# wolf_rev_c.net
KiCad netlist of a schematic drawn in EAGLE
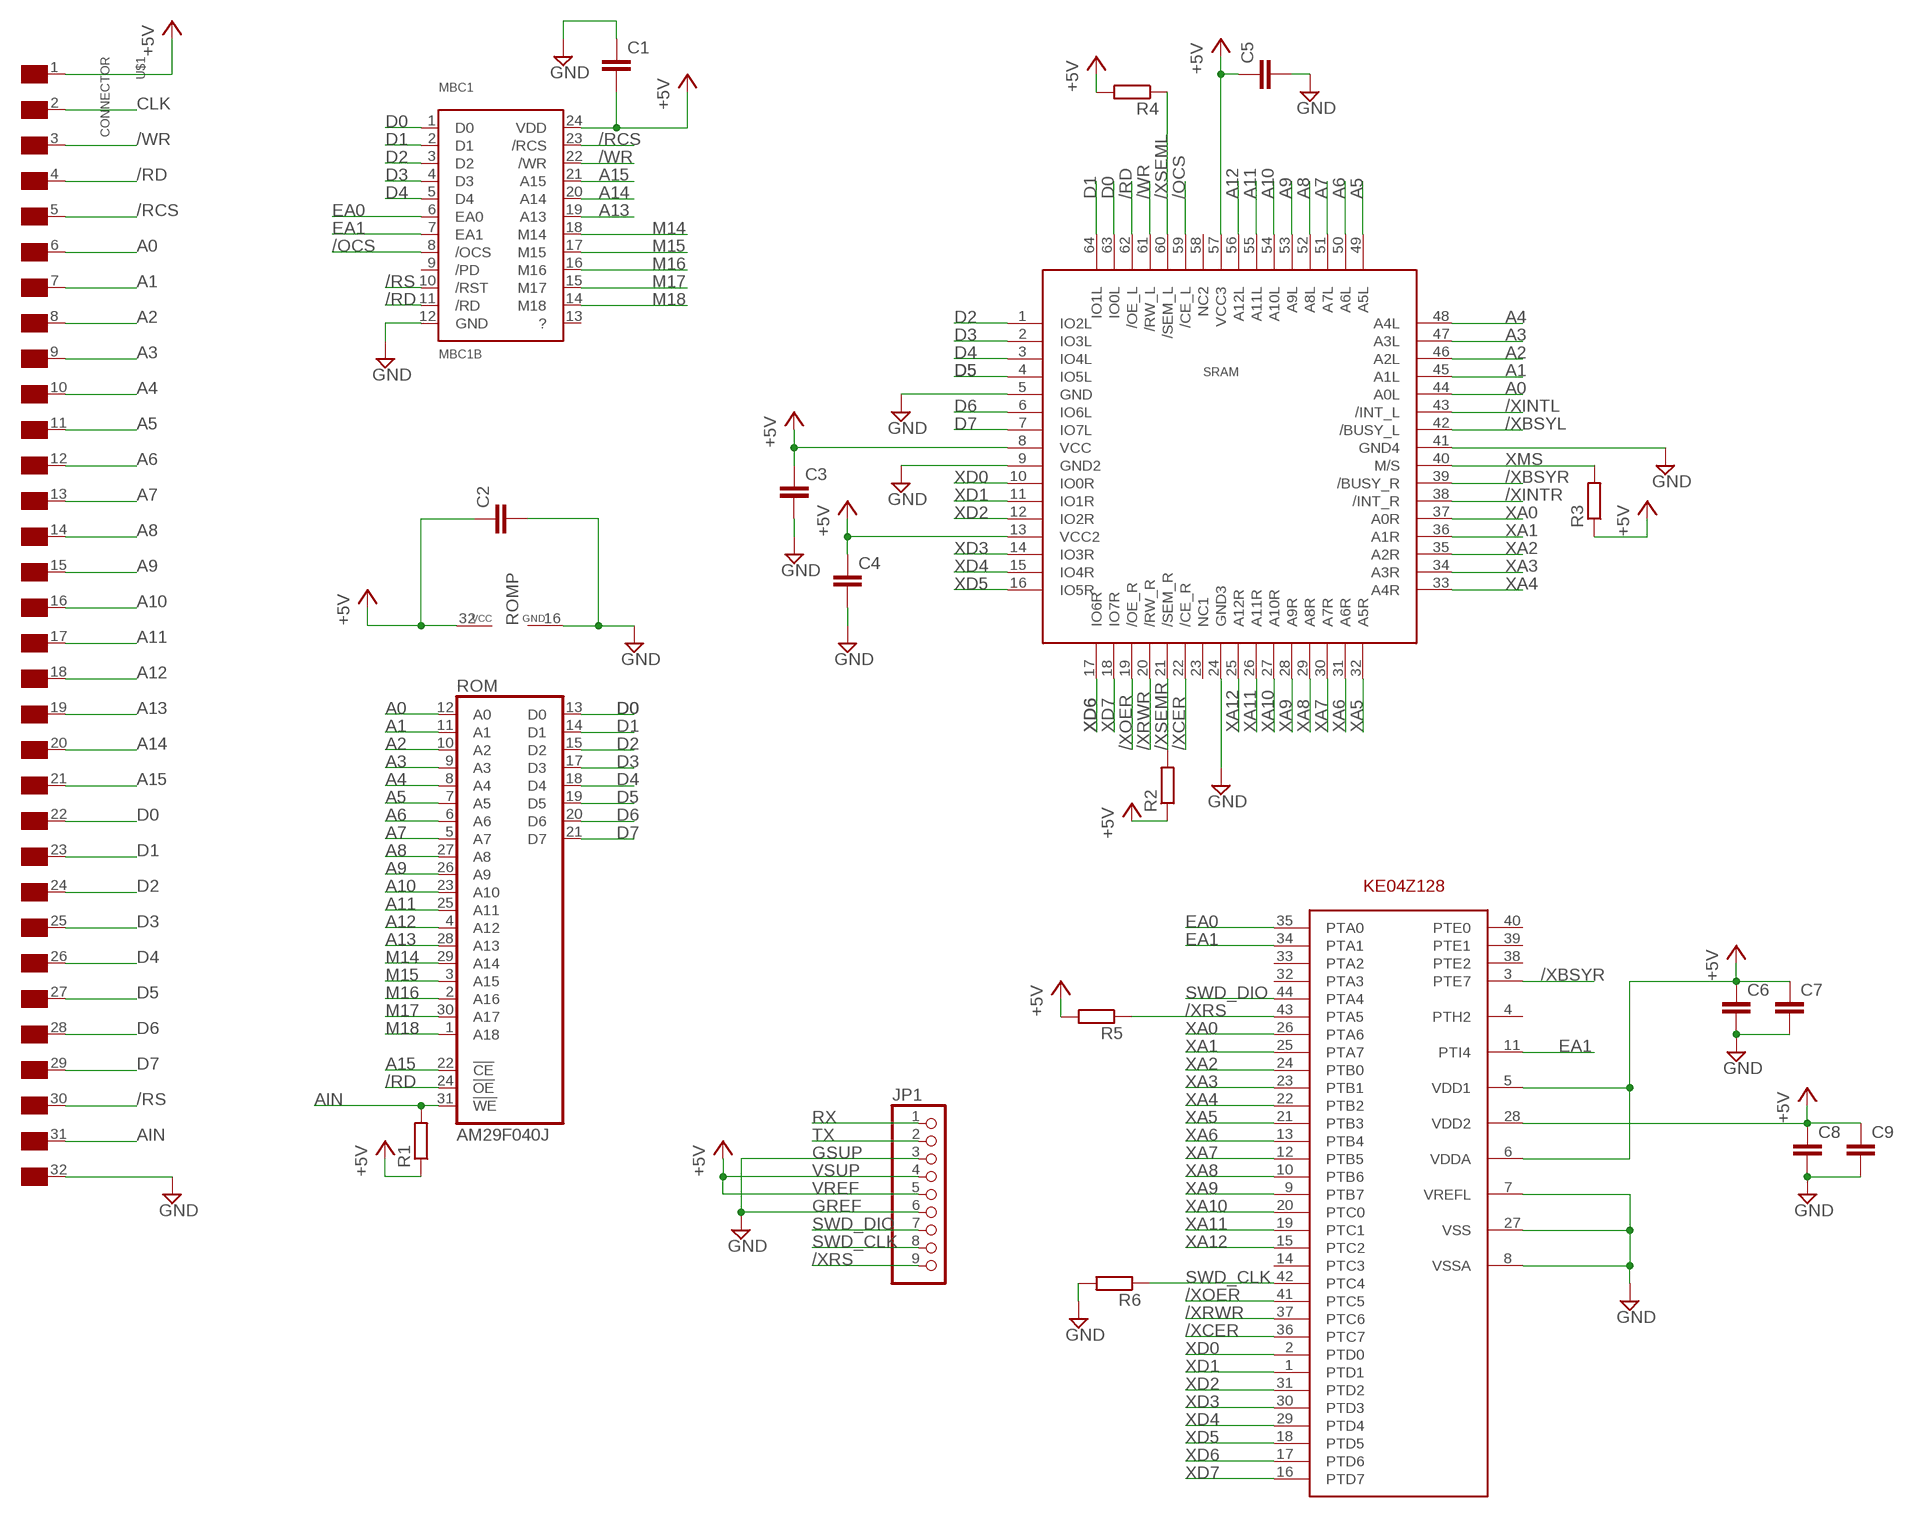
[diagram p0: schematic, sheet 1]

(export (version "E")
  (design (tool "Eeschema 10.0.6"))
  (components
    (comp (ref "C1")
      (value "C-EUC0805")
      (footprint "eagle-import:C0805")
      (libsource (lib "eagle-import") (part "C-EUC0805"))
    )
    (comp (ref "C2")
      (value "C-EUC0805")
      (footprint "eagle-import:C0805")
      (libsource (lib "eagle-import") (part "C-EUC0805"))
    )
    (comp (ref "C3")
      (value "C-EUC0805")
      (footprint "eagle-import:C0805")
      (libsource (lib "eagle-import") (part "C-EUC0805"))
    )
    (comp (ref "C4")
      (value "C-EUC0805")
      (footprint "eagle-import:C0805")
      (libsource (lib "eagle-import") (part "C-EUC0805"))
    )
    (comp (ref "C5")
      (value "C-EUC0805")
      (footprint "eagle-import:C0805")
      (libsource (lib "eagle-import") (part "C-EUC0805"))
    )
    (comp (ref "C6")
      (value "C-EUC0805")
      (footprint "eagle-import:C0805")
      (libsource (lib "eagle-import") (part "C-EUC0805"))
    )
    (comp (ref "C7")
      (value "C-EUC0805")
      (footprint "eagle-import:C0805")
      (libsource (lib "eagle-import") (part "C-EUC0805"))
    )
    (comp (ref "C8")
      (value "C-EUC0805")
      (footprint "eagle-import:C0805")
      (libsource (lib "eagle-import") (part "C-EUC0805"))
    )
    (comp (ref "C9")
      (value "C-EUC0805")
      (footprint "eagle-import:C0805")
      (libsource (lib "eagle-import") (part "C-EUC0805"))
    )
    (comp (ref "JP1")
      (value "PINHD-1X9")
      (footprint "eagle-import:1X09")
      (libsource (lib "eagle-import") (part "PINHD-1X9"))
    )
    (comp (ref "KE04Z128")
      (value "KE04Z128")
      (footprint "eagle-import:TQFP44")
      (libsource (lib "eagle-import") (part "KE04Z128VLD4"))
    )
    (comp (ref "MBC1")
      (value "MBC1B")
      (footprint "eagle-import:MBC1B")
      (libsource (lib "eagle-import") (part "MBC1B"))
    )
    (comp (ref "R1")
      (value "R-EU_R0805")
      (footprint "eagle-import:R0805")
      (libsource (lib "eagle-import") (part "R-EU_R0805"))
    )
    (comp (ref "R2")
      (value "R-EU_R0805")
      (footprint "eagle-import:R0805")
      (libsource (lib "eagle-import") (part "R-EU_R0805"))
    )
    (comp (ref "R3")
      (value "R-EU_R0805")
      (footprint "eagle-import:R0805")
      (libsource (lib "eagle-import") (part "R-EU_R0805"))
    )
    (comp (ref "R4")
      (value "R-EU_R0805")
      (footprint "eagle-import:R0805")
      (libsource (lib "eagle-import") (part "R-EU_R0805"))
    )
    (comp (ref "R5")
      (value "R-EU_R0805")
      (footprint "eagle-import:R0805")
      (libsource (lib "eagle-import") (part "R-EU_R0805"))
    )
    (comp (ref "R6")
      (value "R-EU_R0805")
      (footprint "eagle-import:R0805")
      (libsource (lib "eagle-import") (part "R-EU_R0805"))
    )
    (comp (ref "ROM")
      (value "AM29F040J")
      (footprint "eagle-import:PLCC32R")
      (libsource (lib "eagle-import") (part "AM29F040J"))
    )
    (comp (ref "SRAM")
      (value "CY7C144E")
      (footprint "eagle-import:TQFP64")
      (libsource (lib "eagle-import") (part "CY7C144E"))
    )
    (comp (ref "U$1")
      (value "CONNECTOR")
      (footprint "eagle-import:CONNECTOR")
      (libsource (lib "eagle-import") (part "CONNECTOR"))
    )
  )
  (nets
    (net (code "1") (name "+5V") (class "Default")
      (node (ref "C1") (pin "2") (pinfunction "2_2") (pintype "passive"))
      (node (ref "C2") (pin "1") (pinfunction "1_1") (pintype "passive"))
      (node (ref "C3") (pin "1") (pinfunction "1_1") (pintype "passive"))
      (node (ref "C4") (pin "1") (pinfunction "1_1") (pintype "passive"))
      (node (ref "C5") (pin "1") (pinfunction "1_1") (pintype "passive"))
      (node (ref "C6") (pin "1") (pinfunction "1_1") (pintype "passive"))
      (node (ref "C7") (pin "1") (pinfunction "1_1") (pintype "passive"))
      (node (ref "C8") (pin "1") (pinfunction "1_1") (pintype "passive"))
      (node (ref "C9") (pin "1") (pinfunction "1_1") (pintype "passive"))
      (node (ref "JP1") (pin "4") (pinfunction "4_4") (pintype "passive"))
      (node (ref "JP1") (pin "5") (pinfunction "5_5") (pintype "passive"))
      (node (ref "KE04Z128") (pin "28") (pinfunction "VDD2_28") (pintype "bidirectional"))
      (node (ref "KE04Z128") (pin "5") (pinfunction "VDD1_5") (pintype "bidirectional"))
      (node (ref "KE04Z128") (pin "6") (pinfunction "VDDA_6") (pintype "bidirectional"))
      (node (ref "MBC1") (pin "24") (pinfunction "VDD_24") (pintype "power_in"))
      (node (ref "R1") (pin "1") (pinfunction "1_1") (pintype "passive"))
      (node (ref "R2") (pin "1") (pinfunction "1_1") (pintype "passive"))
      (node (ref "R3") (pin "1") (pinfunction "1_1") (pintype "passive"))
      (node (ref "R4") (pin "2") (pinfunction "2_2") (pintype "passive"))
      (node (ref "R5") (pin "2") (pinfunction "2_2") (pintype "passive"))
      (node (ref "ROM") (pin "32") (pinfunction "VCC_32") (pintype "power_in"))
      (node (ref "SRAM") (pin "13") (pinfunction "VCC2_13") (pintype "bidirectional"))
      (node (ref "SRAM") (pin "57") (pinfunction "VCC3_57") (pintype "bidirectional"))
      (node (ref "SRAM") (pin "8") (pinfunction "VCC_8") (pintype "bidirectional"))
      (node (ref "U$1") (pin "1") (pinfunction "VDD_1") (pintype "power_in"))
    )
    (net (code "2") (name "/A0") (class "Default")
      (node (ref "ROM") (pin "12") (pinfunction "A0_12") (pintype "input"))
      (node (ref "SRAM") (pin "44") (pinfunction "A0L_44") (pintype "bidirectional"))
      (node (ref "U$1") (pin "6") (pinfunction "A0_6") (pintype "bidirectional"))
    )
    (net (code "3") (name "/A1") (class "Default")
      (node (ref "ROM") (pin "11") (pinfunction "A1_11") (pintype "input"))
      (node (ref "SRAM") (pin "45") (pinfunction "A1L_45") (pintype "bidirectional"))
      (node (ref "U$1") (pin "7") (pinfunction "A1_7") (pintype "bidirectional"))
    )
    (net (code "4") (name "/A2") (class "Default")
      (node (ref "ROM") (pin "10") (pinfunction "A2_10") (pintype "input"))
      (node (ref "SRAM") (pin "46") (pinfunction "A2L_46") (pintype "bidirectional"))
      (node (ref "U$1") (pin "8") (pinfunction "A2_8") (pintype "bidirectional"))
    )
    (net (code "5") (name "/A3") (class "Default")
      (node (ref "ROM") (pin "9") (pinfunction "A3_9") (pintype "input"))
      (node (ref "SRAM") (pin "47") (pinfunction "A3L_47") (pintype "bidirectional"))
      (node (ref "U$1") (pin "9") (pinfunction "A3_9") (pintype "bidirectional"))
    )
    (net (code "6") (name "/A4") (class "Default")
      (node (ref "ROM") (pin "8") (pinfunction "A4_8") (pintype "input"))
      (node (ref "SRAM") (pin "48") (pinfunction "A4L_48") (pintype "bidirectional"))
      (node (ref "U$1") (pin "10") (pinfunction "A4_10") (pintype "bidirectional"))
    )
    (net (code "7") (name "/A5") (class "Default")
      (node (ref "ROM") (pin "7") (pinfunction "A5_7") (pintype "input"))
      (node (ref "SRAM") (pin "49") (pinfunction "A5L_49") (pintype "bidirectional"))
      (node (ref "U$1") (pin "11") (pinfunction "A5_11") (pintype "bidirectional"))
    )
    (net (code "8") (name "/A6") (class "Default")
      (node (ref "ROM") (pin "6") (pinfunction "A6_6") (pintype "input"))
      (node (ref "SRAM") (pin "50") (pinfunction "A6L_50") (pintype "bidirectional"))
      (node (ref "U$1") (pin "12") (pinfunction "A6_12") (pintype "bidirectional"))
    )
    (net (code "9") (name "/A7") (class "Default")
      (node (ref "ROM") (pin "5") (pinfunction "A7_5") (pintype "input"))
      (node (ref "SRAM") (pin "51") (pinfunction "A7L_51") (pintype "bidirectional"))
      (node (ref "U$1") (pin "13") (pinfunction "A7_13") (pintype "bidirectional"))
    )
    (net (code "10") (name "/A8") (class "Default")
      (node (ref "ROM") (pin "27") (pinfunction "A8_27") (pintype "input"))
      (node (ref "SRAM") (pin "52") (pinfunction "A8L_52") (pintype "bidirectional"))
      (node (ref "U$1") (pin "14") (pinfunction "A8_14") (pintype "bidirectional"))
    )
    (net (code "11") (name "/A9") (class "Default")
      (node (ref "ROM") (pin "26") (pinfunction "A9_26") (pintype "input"))
      (node (ref "SRAM") (pin "53") (pinfunction "A9L_53") (pintype "bidirectional"))
      (node (ref "U$1") (pin "15") (pinfunction "A9_15") (pintype "bidirectional"))
    )
    (net (code "12") (name "/A10") (class "Default")
      (node (ref "ROM") (pin "23") (pinfunction "A10_23") (pintype "input"))
      (node (ref "SRAM") (pin "54") (pinfunction "A10L_54") (pintype "bidirectional"))
      (node (ref "U$1") (pin "16") (pinfunction "A10_16") (pintype "bidirectional"))
    )
    (net (code "13") (name "/A11") (class "Default")
      (node (ref "ROM") (pin "25") (pinfunction "A11_25") (pintype "input"))
      (node (ref "SRAM") (pin "55") (pinfunction "A11L_55") (pintype "bidirectional"))
      (node (ref "U$1") (pin "17") (pinfunction "A11_17") (pintype "bidirectional"))
    )
    (net (code "14") (name "/A12") (class "Default")
      (node (ref "ROM") (pin "4") (pinfunction "A12_4") (pintype "input"))
      (node (ref "SRAM") (pin "56") (pinfunction "A12L_56") (pintype "bidirectional"))
      (node (ref "U$1") (pin "18") (pinfunction "A12_18") (pintype "bidirectional"))
    )
    (net (code "15") (name "/A13") (class "Default")
      (node (ref "MBC1") (pin "19") (pinfunction "A13_19") (pintype "bidirectional"))
      (node (ref "ROM") (pin "28") (pinfunction "A13_28") (pintype "input"))
      (node (ref "U$1") (pin "19") (pinfunction "A13_19") (pintype "bidirectional"))
    )
    (net (code "16") (name "/A14") (class "Default")
      (node (ref "MBC1") (pin "20") (pinfunction "A14_20") (pintype "bidirectional"))
      (node (ref "U$1") (pin "20") (pinfunction "A14_20") (pintype "bidirectional"))
    )
    (net (code "17") (name "/A15") (class "Default")
      (node (ref "MBC1") (pin "21") (pinfunction "A15_21") (pintype "bidirectional"))
      (node (ref "ROM") (pin "22") (pinfunction "~{CE}_22") (pintype "input"))
      (node (ref "U$1") (pin "21") (pinfunction "A15_21") (pintype "bidirectional"))
    )
    (net (code "18") (name "/AIN") (class "Default")
      (node (ref "R1") (pin "2") (pinfunction "2_2") (pintype "passive"))
      (node (ref "ROM") (pin "31") (pinfunction "~{WE}_31") (pintype "input"))
      (node (ref "U$1") (pin "31") (pinfunction "VIN_31") (pintype "bidirectional"))
    )
    (net (code "20") (name "/CLK") (class "Default")
      (node (ref "U$1") (pin "2") (pinfunction "NC_2") (pintype "no_connect"))
    )
    (net (code "21") (name "/D0") (class "Default")
      (node (ref "MBC1") (pin "1") (pinfunction "D0_1") (pintype "bidirectional"))
      (node (ref "ROM") (pin "13") (pinfunction "D0_13") (pintype "tri_state"))
      (node (ref "SRAM") (pin "63") (pinfunction "IO0L_63") (pintype "bidirectional"))
      (node (ref "U$1") (pin "22") (pinfunction "D0_22") (pintype "bidirectional"))
    )
    (net (code "22") (name "/D1") (class "Default")
      (node (ref "MBC1") (pin "2") (pinfunction "D1_2") (pintype "bidirectional"))
      (node (ref "ROM") (pin "14") (pinfunction "D1_14") (pintype "tri_state"))
      (node (ref "SRAM") (pin "64") (pinfunction "IO1L_64") (pintype "bidirectional"))
      (node (ref "U$1") (pin "23") (pinfunction "D1_23") (pintype "bidirectional"))
    )
    (net (code "23") (name "/D2") (class "Default")
      (node (ref "MBC1") (pin "3") (pinfunction "D2_3") (pintype "bidirectional"))
      (node (ref "ROM") (pin "15") (pinfunction "D2_15") (pintype "tri_state"))
      (node (ref "SRAM") (pin "1") (pinfunction "IO2L_1") (pintype "bidirectional"))
      (node (ref "U$1") (pin "24") (pinfunction "D2_24") (pintype "bidirectional"))
    )
    (net (code "24") (name "/D3") (class "Default")
      (node (ref "MBC1") (pin "4") (pinfunction "D3_4") (pintype "bidirectional"))
      (node (ref "ROM") (pin "17") (pinfunction "D3_17") (pintype "tri_state"))
      (node (ref "SRAM") (pin "2") (pinfunction "IO3L_2") (pintype "bidirectional"))
      (node (ref "U$1") (pin "25") (pinfunction "D3_25") (pintype "bidirectional"))
    )
    (net (code "25") (name "/D4") (class "Default")
      (node (ref "MBC1") (pin "5") (pinfunction "D4_5") (pintype "bidirectional"))
      (node (ref "ROM") (pin "18") (pinfunction "D4_18") (pintype "tri_state"))
      (node (ref "SRAM") (pin "3") (pinfunction "IO4L_3") (pintype "bidirectional"))
      (node (ref "U$1") (pin "26") (pinfunction "D4_26") (pintype "bidirectional"))
    )
    (net (code "26") (name "/D5") (class "Default")
      (node (ref "ROM") (pin "19") (pinfunction "D5_19") (pintype "tri_state"))
      (node (ref "SRAM") (pin "4") (pinfunction "IO5L_4") (pintype "bidirectional"))
      (node (ref "U$1") (pin "27") (pinfunction "D5_27") (pintype "bidirectional"))
    )
    (net (code "27") (name "/D6") (class "Default")
      (node (ref "ROM") (pin "20") (pinfunction "D6_20") (pintype "tri_state"))
      (node (ref "SRAM") (pin "6") (pinfunction "IO6L_6") (pintype "bidirectional"))
      (node (ref "U$1") (pin "28") (pinfunction "D6_28") (pintype "bidirectional"))
    )
    (net (code "28") (name "/D7") (class "Default")
      (node (ref "ROM") (pin "21") (pinfunction "D7_21") (pintype "tri_state"))
      (node (ref "SRAM") (pin "7") (pinfunction "IO7L_7") (pintype "bidirectional"))
      (node (ref "U$1") (pin "29") (pinfunction "D7_29") (pintype "bidirectional"))
    )
    (net (code "29") (name "/EA0") (class "Default")
      (node (ref "KE04Z128") (pin "35") (pinfunction "PTA0_35") (pintype "bidirectional"))
      (node (ref "MBC1") (pin "6") (pinfunction "EA0_6") (pintype "bidirectional"))
    )
    (net (code "30") (name "/EA1") (class "Default")
      (node (ref "KE04Z128") (pin "11") (pinfunction "PTI4_11") (pintype "bidirectional"))
      (node (ref "KE04Z128") (pin "34") (pinfunction "PTA1_34") (pintype "bidirectional"))
      (node (ref "MBC1") (pin "7") (pinfunction "EA1_7") (pintype "bidirectional"))
    )
    (net (code "31") (name "/M14") (class "Default")
      (node (ref "MBC1") (pin "18") (pinfunction "M14_18") (pintype "bidirectional"))
      (node (ref "ROM") (pin "29") (pinfunction "A14_29") (pintype "input"))
    )
    (net (code "32") (name "/M15") (class "Default")
      (node (ref "MBC1") (pin "17") (pinfunction "M15_17") (pintype "bidirectional"))
      (node (ref "ROM") (pin "3") (pinfunction "A15_3") (pintype "input"))
    )
    (net (code "33") (name "/M16") (class "Default")
      (node (ref "MBC1") (pin "16") (pinfunction "M16_16") (pintype "bidirectional"))
      (node (ref "ROM") (pin "2") (pinfunction "A16_2") (pintype "input"))
    )
    (net (code "34") (name "/M17") (class "Default")
      (node (ref "MBC1") (pin "15") (pinfunction "M17_15") (pintype "bidirectional"))
      (node (ref "ROM") (pin "30") (pinfunction "A17_30") (pintype "input"))
    )
    (net (code "35") (name "/M18") (class "Default")
      (node (ref "MBC1") (pin "14") (pinfunction "M18_14") (pintype "bidirectional"))
      (node (ref "ROM") (pin "1") (pinfunction "A18_1") (pintype "input"))
    )
    (net (code "36") (name "/RX") (class "Default")
      (node (ref "JP1") (pin "1") (pinfunction "1_1") (pintype "passive"))
    )
    (net (code "37") (name "/SWD_CLK") (class "Default")
      (node (ref "JP1") (pin "8") (pinfunction "8_8") (pintype "passive"))
      (node (ref "KE04Z128") (pin "42") (pinfunction "PTC4_42") (pintype "bidirectional"))
      (node (ref "R6") (pin "1") (pinfunction "1_1") (pintype "passive"))
    )
    (net (code "38") (name "/SWD_DIO") (class "Default")
      (node (ref "JP1") (pin "7") (pinfunction "7_7") (pintype "passive"))
      (node (ref "KE04Z128") (pin "44") (pinfunction "PTA4_44") (pintype "bidirectional"))
    )
    (net (code "39") (name "/TX") (class "Default")
      (node (ref "JP1") (pin "2") (pinfunction "2_2") (pintype "passive"))
    )
    (net (code "40") (name "/XA0") (class "Default")
      (node (ref "KE04Z128") (pin "26") (pinfunction "PTA6_26") (pintype "bidirectional"))
      (node (ref "SRAM") (pin "37") (pinfunction "A0R_37") (pintype "bidirectional"))
    )
    (net (code "41") (name "/XA1") (class "Default")
      (node (ref "KE04Z128") (pin "25") (pinfunction "PTA7_25") (pintype "bidirectional"))
      (node (ref "SRAM") (pin "36") (pinfunction "A1R_36") (pintype "bidirectional"))
    )
    (net (code "42") (name "/XA2") (class "Default")
      (node (ref "KE04Z128") (pin "24") (pinfunction "PTB0_24") (pintype "bidirectional"))
      (node (ref "SRAM") (pin "35") (pinfunction "A2R_35") (pintype "bidirectional"))
    )
    (net (code "43") (name "/XA3") (class "Default")
      (node (ref "KE04Z128") (pin "23") (pinfunction "PTB1_23") (pintype "bidirectional"))
      (node (ref "SRAM") (pin "34") (pinfunction "A3R_34") (pintype "bidirectional"))
    )
    (net (code "44") (name "/XA4") (class "Default")
      (node (ref "KE04Z128") (pin "22") (pinfunction "PTB2_22") (pintype "bidirectional"))
      (node (ref "SRAM") (pin "33") (pinfunction "A4R_33") (pintype "bidirectional"))
    )
    (net (code "45") (name "/XA5") (class "Default")
      (node (ref "KE04Z128") (pin "21") (pinfunction "PTB3_21") (pintype "bidirectional"))
      (node (ref "SRAM") (pin "32") (pinfunction "A5R_32") (pintype "bidirectional"))
    )
    (net (code "46") (name "/XA6") (class "Default")
      (node (ref "KE04Z128") (pin "13") (pinfunction "PTB4_13") (pintype "bidirectional"))
      (node (ref "SRAM") (pin "31") (pinfunction "A6R_31") (pintype "bidirectional"))
    )
    (net (code "47") (name "/XA7") (class "Default")
      (node (ref "KE04Z128") (pin "12") (pinfunction "PTB5_12") (pintype "bidirectional"))
      (node (ref "SRAM") (pin "30") (pinfunction "A7R_30") (pintype "bidirectional"))
    )
    (net (code "48") (name "/XA8") (class "Default")
      (node (ref "KE04Z128") (pin "10") (pinfunction "PTB6_10") (pintype "bidirectional"))
      (node (ref "SRAM") (pin "29") (pinfunction "A8R_29") (pintype "bidirectional"))
    )
    (net (code "49") (name "/XA9") (class "Default")
      (node (ref "KE04Z128") (pin "9") (pinfunction "PTB7_9") (pintype "bidirectional"))
      (node (ref "SRAM") (pin "28") (pinfunction "A9R_28") (pintype "bidirectional"))
    )
    (net (code "50") (name "/XA10") (class "Default")
      (node (ref "KE04Z128") (pin "20") (pinfunction "PTC0_20") (pintype "bidirectional"))
      (node (ref "SRAM") (pin "27") (pinfunction "A10R_27") (pintype "bidirectional"))
    )
    (net (code "51") (name "/XA11") (class "Default")
      (node (ref "KE04Z128") (pin "19") (pinfunction "PTC1_19") (pintype "bidirectional"))
      (node (ref "SRAM") (pin "26") (pinfunction "A11R_26") (pintype "bidirectional"))
    )
    (net (code "52") (name "/XA12") (class "Default")
      (node (ref "KE04Z128") (pin "15") (pinfunction "PTC2_15") (pintype "bidirectional"))
      (node (ref "SRAM") (pin "25") (pinfunction "A12R_25") (pintype "bidirectional"))
    )
    (net (code "53") (name "/XD0") (class "Default")
      (node (ref "KE04Z128") (pin "2") (pinfunction "PTD0_2") (pintype "bidirectional"))
      (node (ref "SRAM") (pin "10") (pinfunction "IO0R_10") (pintype "bidirectional"))
    )
    (net (code "54") (name "/XD1") (class "Default")
      (node (ref "KE04Z128") (pin "1") (pinfunction "PTD1_1") (pintype "bidirectional"))
      (node (ref "SRAM") (pin "11") (pinfunction "IO1R_11") (pintype "bidirectional"))
    )
    (net (code "55") (name "/XD2") (class "Default")
      (node (ref "KE04Z128") (pin "31") (pinfunction "PTD2_31") (pintype "bidirectional"))
      (node (ref "SRAM") (pin "12") (pinfunction "IO2R_12") (pintype "bidirectional"))
    )
    (net (code "56") (name "/XD3") (class "Default")
      (node (ref "KE04Z128") (pin "30") (pinfunction "PTD3_30") (pintype "bidirectional"))
      (node (ref "SRAM") (pin "14") (pinfunction "IO3R_14") (pintype "bidirectional"))
    )
    (net (code "57") (name "/XD4") (class "Default")
      (node (ref "KE04Z128") (pin "29") (pinfunction "PTD4_29") (pintype "bidirectional"))
      (node (ref "SRAM") (pin "15") (pinfunction "IO4R_15") (pintype "bidirectional"))
    )
    (net (code "58") (name "/XD5") (class "Default")
      (node (ref "KE04Z128") (pin "18") (pinfunction "PTD5_18") (pintype "bidirectional"))
      (node (ref "SRAM") (pin "16") (pinfunction "IO5R_16") (pintype "bidirectional"))
    )
    (net (code "59") (name "/XD6") (class "Default")
      (node (ref "KE04Z128") (pin "17") (pinfunction "PTD6_17") (pintype "bidirectional"))
      (node (ref "SRAM") (pin "17") (pinfunction "IO6R_17") (pintype "bidirectional"))
    )
    (net (code "60") (name "/XD7") (class "Default")
      (node (ref "KE04Z128") (pin "16") (pinfunction "PTD7_16") (pintype "bidirectional"))
      (node (ref "SRAM") (pin "18") (pinfunction "IO7R_18") (pintype "bidirectional"))
    )
    (net (code "61") (name "/XMS") (class "Default")
      (node (ref "R3") (pin "2") (pinfunction "2_2") (pintype "passive"))
      (node (ref "SRAM") (pin "40") (pinfunction "M/S_40") (pintype "bidirectional"))
    )
    (net (code "62") (name "/{slash}OCS") (class "Default")
      (node (ref "MBC1") (pin "8") (pinfunction "/OCS_8") (pintype "bidirectional"))
      (node (ref "SRAM") (pin "59") (pinfunction "/CE_L_59") (pintype "bidirectional"))
    )
    (net (code "63") (name "/{slash}RCS") (class "Default")
      (node (ref "MBC1") (pin "23") (pinfunction "/RCS_23") (pintype "bidirectional"))
      (node (ref "U$1") (pin "5") (pinfunction "/RCS_5") (pintype "bidirectional"))
    )
    (net (code "64") (name "/{slash}RD") (class "Default")
      (node (ref "MBC1") (pin "11") (pinfunction "/RD_11") (pintype "bidirectional"))
      (node (ref "ROM") (pin "24") (pinfunction "~{OE}_24") (pintype "input"))
      (node (ref "SRAM") (pin "62") (pinfunction "/OE_L_62") (pintype "bidirectional"))
      (node (ref "U$1") (pin "4") (pinfunction "/RD_4") (pintype "bidirectional"))
    )
    (net (code "65") (name "/{slash}RS") (class "Default")
      (node (ref "MBC1") (pin "10") (pinfunction "/RST_10") (pintype "bidirectional"))
      (node (ref "U$1") (pin "30") (pinfunction "/RS_30") (pintype "bidirectional"))
    )
    (net (code "66") (name "/{slash}WR") (class "Default")
      (node (ref "MBC1") (pin "22") (pinfunction "/WR_22") (pintype "bidirectional"))
      (node (ref "SRAM") (pin "61") (pinfunction "/RW_L_61") (pintype "bidirectional"))
      (node (ref "U$1") (pin "3") (pinfunction "/WR_3") (pintype "bidirectional"))
    )
    (net (code "67") (name "/{slash}XBSYL") (class "Default")
      (node (ref "SRAM") (pin "42") (pinfunction "/BUSY_L_42") (pintype "bidirectional"))
    )
    (net (code "68") (name "/{slash}XBSYR") (class "Default")
      (node (ref "KE04Z128") (pin "3") (pinfunction "PTE7_3") (pintype "bidirectional"))
      (node (ref "SRAM") (pin "39") (pinfunction "/BUSY_R_39") (pintype "bidirectional"))
    )
    (net (code "69") (name "/{slash}XCER") (class "Default")
      (node (ref "KE04Z128") (pin "36") (pinfunction "PTC7_36") (pintype "bidirectional"))
      (node (ref "SRAM") (pin "22") (pinfunction "/CE_R_22") (pintype "bidirectional"))
    )
    (net (code "70") (name "/{slash}XINTL") (class "Default")
      (node (ref "SRAM") (pin "43") (pinfunction "/INT_L_43") (pintype "bidirectional"))
    )
    (net (code "71") (name "/{slash}XINTR") (class "Default")
      (node (ref "SRAM") (pin "38") (pinfunction "/INT_R_38") (pintype "bidirectional"))
    )
    (net (code "72") (name "/{slash}XOER") (class "Default")
      (node (ref "KE04Z128") (pin "41") (pinfunction "PTC5_41") (pintype "bidirectional"))
      (node (ref "SRAM") (pin "19") (pinfunction "/OE_R_19") (pintype "bidirectional"))
    )
    (net (code "73") (name "/{slash}XRS") (class "Default")
      (node (ref "JP1") (pin "9") (pinfunction "9_9") (pintype "passive"))
      (node (ref "KE04Z128") (pin "43") (pinfunction "PTA5_43") (pintype "bidirectional"))
      (node (ref "R5") (pin "1") (pinfunction "1_1") (pintype "passive"))
    )
    (net (code "74") (name "/{slash}XRWR") (class "Default")
      (node (ref "KE04Z128") (pin "37") (pinfunction "PTC6_37") (pintype "bidirectional"))
      (node (ref "SRAM") (pin "20") (pinfunction "/RW_R_20") (pintype "bidirectional"))
    )
    (net (code "75") (name "/{slash}XSEML") (class "Default")
      (node (ref "R4") (pin "1") (pinfunction "1_1") (pintype "passive"))
      (node (ref "SRAM") (pin "60") (pinfunction "/SEM_L_60") (pintype "bidirectional"))
    )
    (net (code "76") (name "/{slash}XSEMR") (class "Default")
      (node (ref "R2") (pin "2") (pinfunction "2_2") (pintype "passive"))
      (node (ref "SRAM") (pin "21") (pinfunction "/SEM_R_21") (pintype "bidirectional"))
    )
    (net (code "77") (name "GND") (class "Default")
      (node (ref "C1") (pin "1") (pinfunction "1_1") (pintype "passive"))
      (node (ref "C2") (pin "2") (pinfunction "2_2") (pintype "passive"))
      (node (ref "C3") (pin "2") (pinfunction "2_2") (pintype "passive"))
      (node (ref "C4") (pin "2") (pinfunction "2_2") (pintype "passive"))
      (node (ref "C5") (pin "2") (pinfunction "2_2") (pintype "passive"))
      (node (ref "C6") (pin "2") (pinfunction "2_2") (pintype "passive"))
      (node (ref "C7") (pin "2") (pinfunction "2_2") (pintype "passive"))
      (node (ref "C8") (pin "2") (pinfunction "2_2") (pintype "passive"))
      (node (ref "C9") (pin "2") (pinfunction "2_2") (pintype "passive"))
      (node (ref "JP1") (pin "3") (pinfunction "3_3") (pintype "passive"))
      (node (ref "JP1") (pin "6") (pinfunction "6_6") (pintype "passive"))
      (node (ref "KE04Z128") (pin "27") (pinfunction "VSS_27") (pintype "bidirectional"))
      (node (ref "KE04Z128") (pin "7") (pinfunction "VREFL_7") (pintype "bidirectional"))
      (node (ref "KE04Z128") (pin "8") (pinfunction "VSSA_8") (pintype "bidirectional"))
      (node (ref "MBC1") (pin "12") (pinfunction "GND_12") (pintype "power_in"))
      (node (ref "R6") (pin "2") (pinfunction "2_2") (pintype "passive"))
      (node (ref "ROM") (pin "16") (pinfunction "GND_16") (pintype "power_in"))
      (node (ref "SRAM") (pin "24") (pinfunction "GND3_24") (pintype "bidirectional"))
      (node (ref "SRAM") (pin "41") (pinfunction "GND4_41") (pintype "bidirectional"))
      (node (ref "SRAM") (pin "5") (pinfunction "GND_5") (pintype "bidirectional"))
      (node (ref "SRAM") (pin "9") (pinfunction "GND2_9") (pintype "bidirectional"))
      (node (ref "U$1") (pin "32") (pinfunction "GND_32") (pintype "power_in"))
    )
    (net (code "78") (name "unconnected-(KE04Z128-PTA2-Pad33)") (class "Default")
      (node (ref "KE04Z128") (pin "33") (pinfunction "PTA2_33") (pintype "bidirectional"))
    )
    (net (code "79") (name "unconnected-(KE04Z128-PTA3-Pad32)") (class "Default")
      (node (ref "KE04Z128") (pin "32") (pinfunction "PTA3_32") (pintype "bidirectional"))
    )
    (net (code "80") (name "unconnected-(KE04Z128-PTC3-Pad14)") (class "Default")
      (node (ref "KE04Z128") (pin "14") (pinfunction "PTC3_14") (pintype "bidirectional"))
    )
    (net (code "81") (name "unconnected-(KE04Z128-PTE0-Pad40)") (class "Default")
      (node (ref "KE04Z128") (pin "40") (pinfunction "PTE0_40") (pintype "bidirectional"))
    )
    (net (code "82") (name "unconnected-(KE04Z128-PTE1-Pad39)") (class "Default")
      (node (ref "KE04Z128") (pin "39") (pinfunction "PTE1_39") (pintype "bidirectional"))
    )
    (net (code "83") (name "unconnected-(KE04Z128-PTE2-Pad38)") (class "Default")
      (node (ref "KE04Z128") (pin "38") (pinfunction "PTE2_38") (pintype "bidirectional"))
    )
    (net (code "84") (name "unconnected-(KE04Z128-PTH2-Pad4)") (class "Default")
      (node (ref "KE04Z128") (pin "4") (pinfunction "PTH2_4") (pintype "bidirectional"))
    )
    (net (code "85") (name "unconnected-(MBC1-?-Pad13)") (class "Default")
      (node (ref "MBC1") (pin "13") (pinfunction "?_13") (pintype "bidirectional"))
    )
    (net (code "86") (name "unconnected-(MBC1-{slash}PD-Pad9)") (class "Default")
      (node (ref "MBC1") (pin "9") (pinfunction "/PD_9") (pintype "bidirectional"))
    )
    (net (code "87") (name "unconnected-(SRAM-NC1-Pad23)") (class "Default")
      (node (ref "SRAM") (pin "23") (pinfunction "NC1_23") (pintype "bidirectional"))
    )
    (net (code "88") (name "unconnected-(SRAM-NC2-Pad58)") (class "Default")
      (node (ref "SRAM") (pin "58") (pinfunction "NC2_58") (pintype "bidirectional"))
    )
  )
)
